# Inverter.net
KiCad netlist of a schematic drawn in Altium Designer
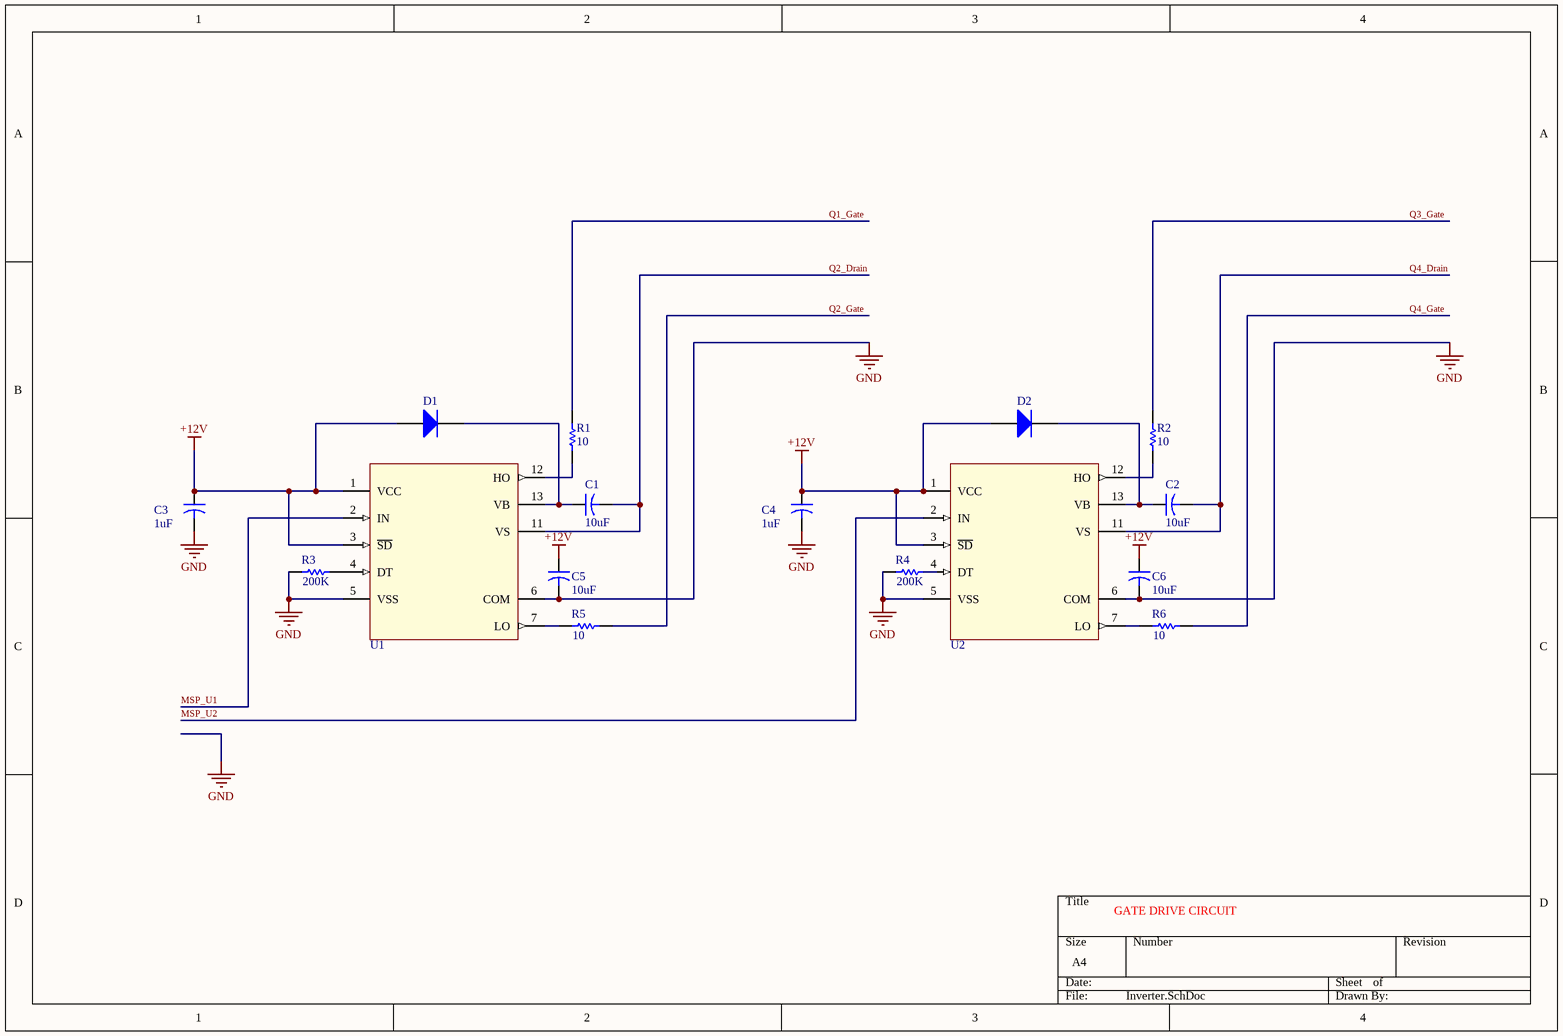
[diagram p0: Inverter.SchDoc]

(export (version "E")
  (design (tool "Eeschema 10.0.6"))
  (components
    (comp (ref "C1")
      (value "10uF")
      (footprint "CAPR5-4X5")
      (description "Capacitor")
      (fields (field (name "Comment") "Cap2") (field (name "PUBLISHER") "Altium Limited"))
      (libsource (lib "Miscellaneous Devices") (part "Cap2"))
    )
    (comp (ref "C2")
      (value "10uF")
      (footprint "CAPR5-4X5")
      (description "Capacitor")
      (fields (field (name "Comment") "Cap2") (field (name "PUBLISHER") "Altium Limited"))
      (libsource (lib "Miscellaneous Devices") (part "Cap2"))
    )
    (comp (ref "C3")
      (value "1uF")
      (footprint "CAPR5-4X5")
      (description "Capacitor")
      (fields (field (name "Comment") "Cap2") (field (name "PUBLISHER") "Altium Limited"))
      (libsource (lib "Miscellaneous Devices") (part "Cap2"))
    )
    (comp (ref "C4")
      (value "1uF")
      (footprint "CAPR5-4X5")
      (description "Capacitor")
      (fields (field (name "Comment") "Cap2") (field (name "PUBLISHER") "Altium Limited"))
      (libsource (lib "Miscellaneous Devices") (part "Cap2"))
    )
    (comp (ref "C5")
      (value "10uF")
      (footprint "CAPR5-4X5")
      (description "Capacitor")
      (fields (field (name "Comment") "Cap2") (field (name "PUBLISHER") "Altium Limited"))
      (libsource (lib "Miscellaneous Devices") (part "Cap2"))
    )
    (comp (ref "C6")
      (value "10uF")
      (footprint "CAPR5-4X5")
      (description "Capacitor")
      (fields (field (name "Comment") "Cap2") (field (name "PUBLISHER") "Altium Limited"))
      (libsource (lib "Miscellaneous Devices") (part "Cap2"))
    )
    (comp (ref "D1")
      (value "Diode")
      (footprint "SMC")
      (description "Default Diode")
      (fields (field (name "PUBLISHER") "Altium Limited"))
      (libsource (lib "Miscellaneous Devices") (part "Diode"))
    )
    (comp (ref "D2")
      (value "Diode")
      (footprint "SMC")
      (description "Default Diode")
      (fields (field (name "PUBLISHER") "Altium Limited"))
      (libsource (lib "Miscellaneous Devices") (part "Diode"))
    )
    (comp (ref "R1")
      (value "10")
      (footprint "AXIAL-0.3")
      (description "Resistor")
      (fields (field (name "Comment") "Res1") (field (name "PUBLISHER") "Altium Limited"))
      (libsource (lib "Miscellaneous Devices") (part "Res1"))
    )
    (comp (ref "R2")
      (value "10")
      (footprint "AXIAL-0.3")
      (description "Resistor")
      (fields (field (name "Comment") "Res1") (field (name "PUBLISHER") "Altium Limited"))
      (libsource (lib "Miscellaneous Devices") (part "Res1"))
    )
    (comp (ref "R3")
      (value "200K")
      (footprint "AXIAL-0.3")
      (description "Resistor")
      (fields (field (name "Comment") "Res1") (field (name "PUBLISHER") "Altium Limited"))
      (libsource (lib "Miscellaneous Devices") (part "Res1"))
    )
    (comp (ref "R4")
      (value "200K")
      (footprint "AXIAL-0.3")
      (description "Resistor")
      (fields (field (name "Comment") "Res1") (field (name "PUBLISHER") "Altium Limited"))
      (libsource (lib "Miscellaneous Devices") (part "Res1"))
    )
    (comp (ref "R5")
      (value "10")
      (footprint "AXIAL-0.3")
      (description "Resistor")
      (fields (field (name "Comment") "Res1") (field (name "PUBLISHER") "Altium Limited"))
      (libsource (lib "Miscellaneous Devices") (part "Res1"))
    )
    (comp (ref "R6")
      (value "10")
      (footprint "AXIAL-0.3")
      (description "Resistor")
      (fields (field (name "Comment") "Res1") (field (name "PUBLISHER") "Altium Limited"))
      (libsource (lib "Miscellaneous Devices") (part "Res1"))
    )
    (comp (ref "U1")
      (value "IR21094")
      (description "Half bridge gate driver")
      (libsource (lib "*") (part "IR21094"))
    )
    (comp (ref "U2")
      (value "IR21094")
      (description "Half bridge gate driver")
      (libsource (lib "*") (part "IR21094"))
    )
  )
  (nets
    (net (code "1") (name "+12V") (class "Default")
      (node (ref "C3") (pin "1") (pinfunction "1_1") (pintype "passive"))
      (node (ref "C4") (pin "1") (pinfunction "1_1") (pintype "passive"))
      (node (ref "C5") (pin "1") (pinfunction "1_1") (pintype "passive"))
      (node (ref "C6") (pin "1") (pinfunction "1_1") (pintype "passive"))
      (node (ref "D1") (pin "1") (pinfunction "A_1") (pintype "passive"))
      (node (ref "D2") (pin "1") (pinfunction "A_1") (pintype "passive"))
      (node (ref "U1") (pin "1") (pinfunction "VCC_1") (pintype "power_in"))
      (node (ref "U1") (pin "3") (pinfunction "~{SD}_3") (pintype "input"))
      (node (ref "U2") (pin "1") (pinfunction "VCC_1") (pintype "power_in"))
      (node (ref "U2") (pin "3") (pinfunction "~{SD}_3") (pintype "input"))
    )
    (net (code "2") (name "/MSP_U1") (class "Default")
      (node (ref "U1") (pin "2") (pinfunction "IN_2") (pintype "input"))
    )
    (net (code "3") (name "/MSP_U2") (class "Default")
      (node (ref "U2") (pin "2") (pinfunction "IN_2") (pintype "input"))
    )
    (net (code "4") (name "/Q1_Gate") (class "Default")
      (node (ref "R1") (pin "2") (pinfunction "2_2") (pintype "passive"))
    )
    (net (code "5") (name "/Q2_Drain") (class "Default")
      (node (ref "C1") (pin "2") (pinfunction "2_2") (pintype "passive"))
      (node (ref "U1") (pin "11") (pinfunction "VS_11") (pintype "power_in"))
    )
    (net (code "6") (name "/Q2_Gate") (class "Default")
      (node (ref "R5") (pin "2") (pinfunction "2_2") (pintype "passive"))
    )
    (net (code "7") (name "/Q3_Gate") (class "Default")
      (node (ref "R2") (pin "2") (pinfunction "2_2") (pintype "passive"))
    )
    (net (code "8") (name "/Q4_Drain") (class "Default")
      (node (ref "C2") (pin "2") (pinfunction "2_2") (pintype "passive"))
      (node (ref "U2") (pin "11") (pinfunction "VS_11") (pintype "power_in"))
    )
    (net (code "9") (name "/Q4_Gate") (class "Default")
      (node (ref "R6") (pin "2") (pinfunction "2_2") (pintype "passive"))
    )
    (net (code "10") (name "GND") (class "Default")
      (node (ref "C3") (pin "2") (pinfunction "2_2") (pintype "passive"))
      (node (ref "C4") (pin "2") (pinfunction "2_2") (pintype "passive"))
      (node (ref "C5") (pin "2") (pinfunction "2_2") (pintype "passive"))
      (node (ref "C6") (pin "2") (pinfunction "2_2") (pintype "passive"))
      (node (ref "R3") (pin "1") (pinfunction "1_1") (pintype "passive"))
      (node (ref "R4") (pin "1") (pinfunction "1_1") (pintype "passive"))
      (node (ref "U1") (pin "5") (pinfunction "VSS_5") (pintype "power_in"))
      (node (ref "U1") (pin "6") (pinfunction "COM_6") (pintype "power_in"))
      (node (ref "U2") (pin "5") (pinfunction "VSS_5") (pintype "power_in"))
      (node (ref "U2") (pin "6") (pinfunction "COM_6") (pintype "power_in"))
    )
    (net (code "11") (name "Net-(D1-K)") (class "Default")
      (node (ref "C1") (pin "1") (pinfunction "1_1") (pintype "passive"))
      (node (ref "D1") (pin "2") (pinfunction "K_2") (pintype "passive"))
      (node (ref "U1") (pin "13") (pinfunction "VB_13") (pintype "power_in"))
    )
    (net (code "12") (name "Net-(D2-K)") (class "Default")
      (node (ref "C2") (pin "1") (pinfunction "1_1") (pintype "passive"))
      (node (ref "D2") (pin "2") (pinfunction "K_2") (pintype "passive"))
      (node (ref "U2") (pin "13") (pinfunction "VB_13") (pintype "power_in"))
    )
    (net (code "13") (name "Net-(U1-DT)") (class "Default")
      (node (ref "R3") (pin "2") (pinfunction "2_2") (pintype "passive"))
      (node (ref "U1") (pin "4") (pinfunction "DT_4") (pintype "input"))
    )
    (net (code "14") (name "Net-(U1-HO)") (class "Default")
      (node (ref "R1") (pin "1") (pinfunction "1_1") (pintype "passive"))
      (node (ref "U1") (pin "12") (pinfunction "HO_12") (pintype "output"))
    )
    (net (code "15") (name "Net-(U1-LO)") (class "Default")
      (node (ref "R5") (pin "1") (pinfunction "1_1") (pintype "passive"))
      (node (ref "U1") (pin "7") (pinfunction "LO_7") (pintype "output"))
    )
    (net (code "16") (name "Net-(U2-DT)") (class "Default")
      (node (ref "R4") (pin "2") (pinfunction "2_2") (pintype "passive"))
      (node (ref "U2") (pin "4") (pinfunction "DT_4") (pintype "input"))
    )
    (net (code "17") (name "Net-(U2-HO)") (class "Default")
      (node (ref "R2") (pin "1") (pinfunction "1_1") (pintype "passive"))
      (node (ref "U2") (pin "12") (pinfunction "HO_12") (pintype "output"))
    )
    (net (code "18") (name "Net-(U2-LO)") (class "Default")
      (node (ref "R6") (pin "1") (pinfunction "1_1") (pintype "passive"))
      (node (ref "U2") (pin "7") (pinfunction "LO_7") (pintype "output"))
    )
    (net (code "19") (name "unconnected-(U1-NC-Pad8)") (class "Default")
      (node (ref "U1") (pin "8") (pinfunction "NC_8") (pintype "tri_state"))
    )
    (net (code "20") (name "unconnected-(U1-NC-Pad9)") (class "Default")
      (node (ref "U1") (pin "9") (pinfunction "NC_9") (pintype "tri_state"))
    )
    (net (code "21") (name "unconnected-(U1-NC-Pad10)") (class "Default")
      (node (ref "U1") (pin "10") (pinfunction "NC_10") (pintype "tri_state"))
    )
    (net (code "22") (name "unconnected-(U1-NC-Pad14)") (class "Default")
      (node (ref "U1") (pin "14") (pinfunction "NC_14") (pintype "tri_state"))
    )
    (net (code "23") (name "unconnected-(U2-NC-Pad8)") (class "Default")
      (node (ref "U2") (pin "8") (pinfunction "NC_8") (pintype "tri_state"))
    )
    (net (code "24") (name "unconnected-(U2-NC-Pad9)") (class "Default")
      (node (ref "U2") (pin "9") (pinfunction "NC_9") (pintype "tri_state"))
    )
    (net (code "25") (name "unconnected-(U2-NC-Pad10)") (class "Default")
      (node (ref "U2") (pin "10") (pinfunction "NC_10") (pintype "tri_state"))
    )
    (net (code "26") (name "unconnected-(U2-NC-Pad14)") (class "Default")
      (node (ref "U2") (pin "14") (pinfunction "NC_14") (pintype "tri_state"))
    )
  )
)
